# Sheet3.net
KiCad netlist of a schematic drawn in Altium Designer
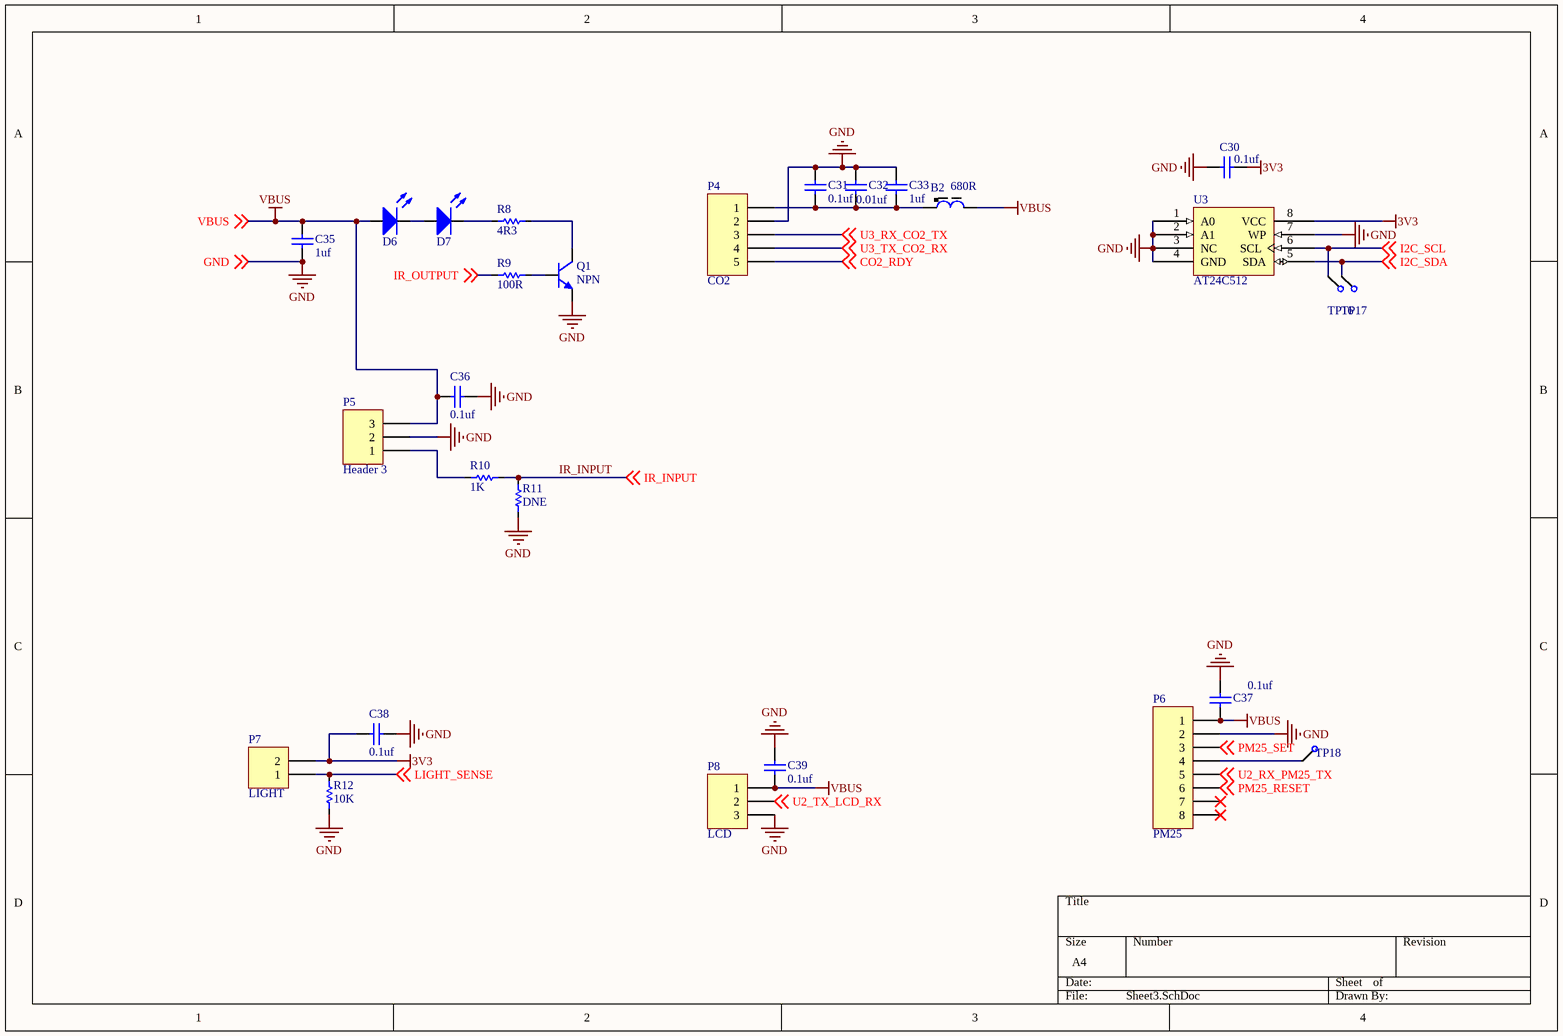
[diagram p0: Sheet3.SchDoc]

(export (version "E")
  (design (tool "Eeschema 10.0.6"))
  (components
    (comp (ref "B2") (value "680R") (footprint "L0603") (libsource (lib "liber") (part "L")))
    (comp (ref "C30")
      (value "0.1uf")
      (footprint "C0603")
      (description "Capacitor")
      (libsource (lib "liber") (part "Cap"))
    )
    (comp (ref "C31")
      (value "0.1uf")
      (footprint "C0603")
      (description "Capacitor")
      (libsource (lib "liber") (part "Cap"))
    )
    (comp (ref "C32")
      (value "0.01uf")
      (footprint "C0603")
      (description "Capacitor")
      (libsource (lib "liber") (part "Cap"))
    )
    (comp (ref "C33")
      (value "1uf")
      (footprint "C0603")
      (description "Capacitor")
      (libsource (lib "liber") (part "Cap"))
    )
    (comp (ref "C35")
      (value "1uf")
      (footprint "C0603")
      (description "Capacitor")
      (libsource (lib "liber") (part "Cap"))
    )
    (comp (ref "C36")
      (value "0.1uf")
      (footprint "C0603")
      (description "Capacitor")
      (libsource (lib "liber") (part "Cap"))
    )
    (comp (ref "C37")
      (value "0.1uf")
      (footprint "C0603")
      (description "Capacitor")
      (libsource (lib "liber") (part "Cap"))
    )
    (comp (ref "C38")
      (value "0.1uf")
      (footprint "C0603")
      (description "Capacitor")
      (libsource (lib "liber") (part "Cap"))
    )
    (comp (ref "C39")
      (value "0.1uf")
      (footprint "C0603")
      (description "Capacitor")
      (libsource (lib "liber") (part "Cap"))
    )
    (comp (ref "D6")
      (value "LED-R")
      (footprint "LED_S")
      (description "Typical INFRARED GaAs LED")
      (fields (field (name "PUBLISHER") "Altium Limited"))
      (libsource (lib "liber") (part "LED"))
    )
    (comp (ref "D7")
      (value "LED-R")
      (footprint "LED_S")
      (description "Typical INFRARED GaAs LED")
      (fields (field (name "PUBLISHER") "Altium Limited"))
      (libsource (lib "liber") (part "LED"))
    )
    (comp (ref "P4")
      (value "CO2")
      (footprint "HDR1X5")
      (description "Header, 5-Pin")
      (fields (field (name "PUBLISHER") "Altium Limited"))
      (libsource (lib "Miscellaneous Connectors") (part "Header 5"))
    )
    (comp (ref "P5")
      (value "Header 3")
      (footprint "HDR1X3")
      (description "Header, 3-Pin")
      (fields (field (name "PUBLISHER") "Altium Limited"))
      (libsource (lib "Miscellaneous Connectors") (part "Header 3"))
    )
    (comp (ref "P6")
      (value "PM25")
      (footprint "1.25T-8P")
      (description "Header, 8-Pin")
      (fields (field (name "PUBLISHER") "Altium Limited"))
      (libsource (lib "Miscellaneous Connectors") (part "Header 8"))
    )
    (comp (ref "P7")
      (value "LIGHT")
      (footprint "HDR1X2")
      (description "Header, 2-Pin")
      (fields (field (name "PUBLISHER") "Altium Limited"))
      (libsource (lib "Miscellaneous Connectors") (part "Header 2"))
    )
    (comp (ref "P8")
      (value "LCD")
      (footprint "HDR1X3")
      (description "Header, 3-Pin")
      (fields (field (name "PUBLISHER") "Altium Limited"))
      (libsource (lib "") (part "Header 3_1"))
    )
    (comp (ref "Q1")
      (value "NPN")
      (footprint "SOT23_BJT")
      (description "NPN Bipolar Transistor")
      (fields (field (name "PUBLISHER") "Altium Limited"))
      (libsource (lib "liber") (part "NPN"))
    )
    (comp (ref "R8")
      (value "4R3")
      (footprint "R0805")
      (fields (field (name "PUBLISHER") "Altium Limited"))
      (libsource (lib "liber") (part "Res"))
    )
    (comp (ref "R9")
      (value "100R")
      (footprint "R0603")
      (fields (field (name "PUBLISHER") "Altium Limited"))
      (libsource (lib "liber") (part "Res"))
    )
    (comp (ref "R10")
      (value "1K")
      (footprint "R0603")
      (fields (field (name "PUBLISHER") "Altium Limited"))
      (libsource (lib "liber") (part "Res"))
    )
    (comp (ref "R11")
      (value "DNE")
      (footprint "R0603")
      (fields (field (name "PUBLISHER") "Altium Limited"))
      (libsource (lib "liber") (part "Res"))
    )
    (comp (ref "R12")
      (value "10K")
      (footprint "R0603")
      (fields (field (name "PUBLISHER") "Altium Limited"))
      (libsource (lib "liber") (part "Res"))
    )
    (comp (ref "TP16")
      (value "TestPoint")
      (footprint "TP_0.8")
      (description "一个测试点")
      (libsource (lib "liber") (part "TestPoint"))
    )
    (comp (ref "TP17")
      (value "TestPoint")
      (footprint "TP_0.8")
      (description "一个测试点")
      (libsource (lib "liber") (part "TestPoint"))
    )
    (comp (ref "TP18")
      (value "TestPoint")
      (footprint "TP_0.8")
      (description "一个测试点")
      (libsource (lib "liber") (part "TestPoint"))
    )
    (comp (ref "U3")
      (value "AT24C512")
      (footprint "AT24C02")
      (description "2-wire Serial  EEPROM  512K (65,536 x 8)")
      (libsource (lib "liber") (part "AT24C512"))
    )
  )
  (nets
    (net (code "1") (name "3V3") (class "Default")
      (node (ref "C30") (pin "2") (pinfunction "2_2") (pintype "passive"))
      (node (ref "C38") (pin "2") (pinfunction "2_2") (pintype "passive"))
      (node (ref "P7") (pin "2") (pinfunction "2_2") (pintype "passive"))
      (node (ref "U3") (pin "8") (pinfunction "VCC_8") (pintype "power_in"))
    )
    (net (code "2") (name "CO2_RDY") (class "Default")
      (node (ref "P4") (pin "5") (pinfunction "5_5") (pintype "passive"))
    )
    (net (code "3") (name "GND") (class "Default")
      (node (ref "C30") (pin "1") (pinfunction "1_1") (pintype "passive"))
      (node (ref "C31") (pin "2") (pinfunction "2_2") (pintype "passive"))
      (node (ref "C32") (pin "2") (pinfunction "2_2") (pintype "passive"))
      (node (ref "C33") (pin "2") (pinfunction "2_2") (pintype "passive"))
      (node (ref "C35") (pin "1") (pinfunction "1_1") (pintype "passive"))
      (node (ref "C36") (pin "1") (pinfunction "1_1") (pintype "passive"))
      (node (ref "C37") (pin "2") (pinfunction "2_2") (pintype "passive"))
      (node (ref "C38") (pin "1") (pinfunction "1_1") (pintype "passive"))
      (node (ref "C39") (pin "2") (pinfunction "2_2") (pintype "passive"))
      (node (ref "P4") (pin "2") (pinfunction "2_2") (pintype "passive"))
      (node (ref "P5") (pin "2") (pinfunction "2_2") (pintype "passive"))
      (node (ref "P6") (pin "2") (pinfunction "2_2") (pintype "passive"))
      (node (ref "P8") (pin "3") (pinfunction "3_3") (pintype "passive"))
      (node (ref "Q1") (pin "1") (pinfunction "E_1") (pintype "passive"))
      (node (ref "R11") (pin "1") (pinfunction "1_1") (pintype "passive"))
      (node (ref "R12") (pin "1") (pinfunction "1_1") (pintype "passive"))
      (node (ref "U3") (pin "1") (pinfunction "A0_1") (pintype "input"))
      (node (ref "U3") (pin "2") (pinfunction "A1_2") (pintype "input"))
      (node (ref "U3") (pin "3") (pinfunction "NC_3") (pintype "passive"))
      (node (ref "U3") (pin "4") (pinfunction "GND_4") (pintype "power_in"))
      (node (ref "U3") (pin "7") (pinfunction "WP_7") (pintype "input"))
    )
    (net (code "4") (name "I2C_SCL") (class "Default")
      (node (ref "TP16") (pin "1") (pinfunction "1_1") (pintype "passive"))
      (node (ref "U3") (pin "6") (pinfunction "SCL_6") (pintype "input"))
    )
    (net (code "5") (name "I2C_SDA") (class "Default")
      (node (ref "TP17") (pin "1") (pinfunction "1_1") (pintype "passive"))
      (node (ref "U3") (pin "5") (pinfunction "SDA_5") (pintype "bidirectional"))
    )
    (net (code "6") (name "IR_INPUT") (class "Default")
      (node (ref "R10") (pin "2") (pinfunction "2_2") (pintype "passive"))
      (node (ref "R11") (pin "2") (pinfunction "2_2") (pintype "passive"))
    )
    (net (code "7") (name "IR_OUTPUT") (class "Default")
      (node (ref "R9") (pin "1") (pinfunction "1_1") (pintype "passive"))
    )
    (net (code "8") (name "LIGHT_SENSE") (class "Default")
      (node (ref "P7") (pin "1") (pinfunction "1_1") (pintype "passive"))
      (node (ref "R12") (pin "2") (pinfunction "2_2") (pintype "passive"))
    )
    (net (code "9") (name "Net-(B2-Pad1)") (class "Default")
      (node (ref "B2") (pin "1") (pinfunction "1_1") (pintype "passive"))
      (node (ref "C31") (pin "1") (pinfunction "1_1") (pintype "passive"))
      (node (ref "C32") (pin "1") (pinfunction "1_1") (pintype "passive"))
      (node (ref "C33") (pin "1") (pinfunction "1_1") (pintype "passive"))
      (node (ref "P4") (pin "1") (pinfunction "1_1") (pintype "passive"))
    )
    (net (code "10") (name "Net-(D6-K)") (class "Default")
      (node (ref "D6") (pin "2") (pinfunction "K_2") (pintype "passive"))
      (node (ref "D7") (pin "1") (pinfunction "A_1") (pintype "passive"))
    )
    (net (code "11") (name "Net-(D7-K)") (class "Default")
      (node (ref "D7") (pin "2") (pinfunction "K_2") (pintype "passive"))
      (node (ref "R8") (pin "2") (pinfunction "2_2") (pintype "passive"))
    )
    (net (code "12") (name "Net-(P5-Pad1)") (class "Default")
      (node (ref "P5") (pin "1") (pinfunction "1_1") (pintype "passive"))
      (node (ref "R10") (pin "1") (pinfunction "1_1") (pintype "passive"))
    )
    (net (code "13") (name "Net-(P6-Pad4)") (class "Default")
      (node (ref "P6") (pin "4") (pinfunction "4_4") (pintype "passive"))
      (node (ref "TP18") (pin "1") (pinfunction "1_1") (pintype "passive"))
    )
    (net (code "14") (name "Net-(Q1-B)") (class "Default")
      (node (ref "Q1") (pin "2") (pinfunction "B_2") (pintype "passive"))
      (node (ref "R9") (pin "2") (pinfunction "2_2") (pintype "passive"))
    )
    (net (code "15") (name "Net-(Q1-C)") (class "Default")
      (node (ref "Q1") (pin "3") (pinfunction "C_3") (pintype "passive"))
      (node (ref "R8") (pin "1") (pinfunction "1_1") (pintype "passive"))
    )
    (net (code "16") (name "PM25_RESET") (class "Default")
      (node (ref "P6") (pin "6") (pinfunction "6_6") (pintype "passive"))
    )
    (net (code "17") (name "PM25_SET") (class "Default")
      (node (ref "P6") (pin "3") (pinfunction "3_3") (pintype "passive"))
    )
    (net (code "18") (name "U2_RX_PM25_TX") (class "Default")
      (node (ref "P6") (pin "5") (pinfunction "5_5") (pintype "passive"))
    )
    (net (code "19") (name "U2_TX_LCD_RX") (class "Default")
      (node (ref "P8") (pin "2") (pinfunction "2_2") (pintype "passive"))
    )
    (net (code "20") (name "U3_RX_CO2_TX") (class "Default")
      (node (ref "P4") (pin "3") (pinfunction "3_3") (pintype "passive"))
    )
    (net (code "21") (name "U3_TX_CO2_RX") (class "Default")
      (node (ref "P4") (pin "4") (pinfunction "4_4") (pintype "passive"))
    )
    (net (code "22") (name "VBUS") (class "Default")
      (node (ref "B2") (pin "2") (pinfunction "2_2") (pintype "passive"))
      (node (ref "C35") (pin "2") (pinfunction "2_2") (pintype "passive"))
      (node (ref "C36") (pin "2") (pinfunction "2_2") (pintype "passive"))
      (node (ref "C37") (pin "1") (pinfunction "1_1") (pintype "passive"))
      (node (ref "C39") (pin "1") (pinfunction "1_1") (pintype "passive"))
      (node (ref "D6") (pin "1") (pinfunction "A_1") (pintype "passive"))
      (node (ref "P5") (pin "3") (pinfunction "3_3") (pintype "passive"))
      (node (ref "P6") (pin "1") (pinfunction "1_1") (pintype "passive"))
      (node (ref "P8") (pin "1") (pinfunction "1_1") (pintype "passive"))
    )
    (net (code "23") (name "unconnected-(P6-Pad7)") (class "Default")
      (node (ref "P6") (pin "7") (pinfunction "7_7") (pintype "passive+no_connect"))
    )
    (net (code "24") (name "unconnected-(P6-Pad8)") (class "Default")
      (node (ref "P6") (pin "8") (pinfunction "8_8") (pintype "passive+no_connect"))
    )
  )
)
